# XstractiK_Domination_Player_Connector_V1.net
KiCad netlist of a schematic drawn in EAGLE
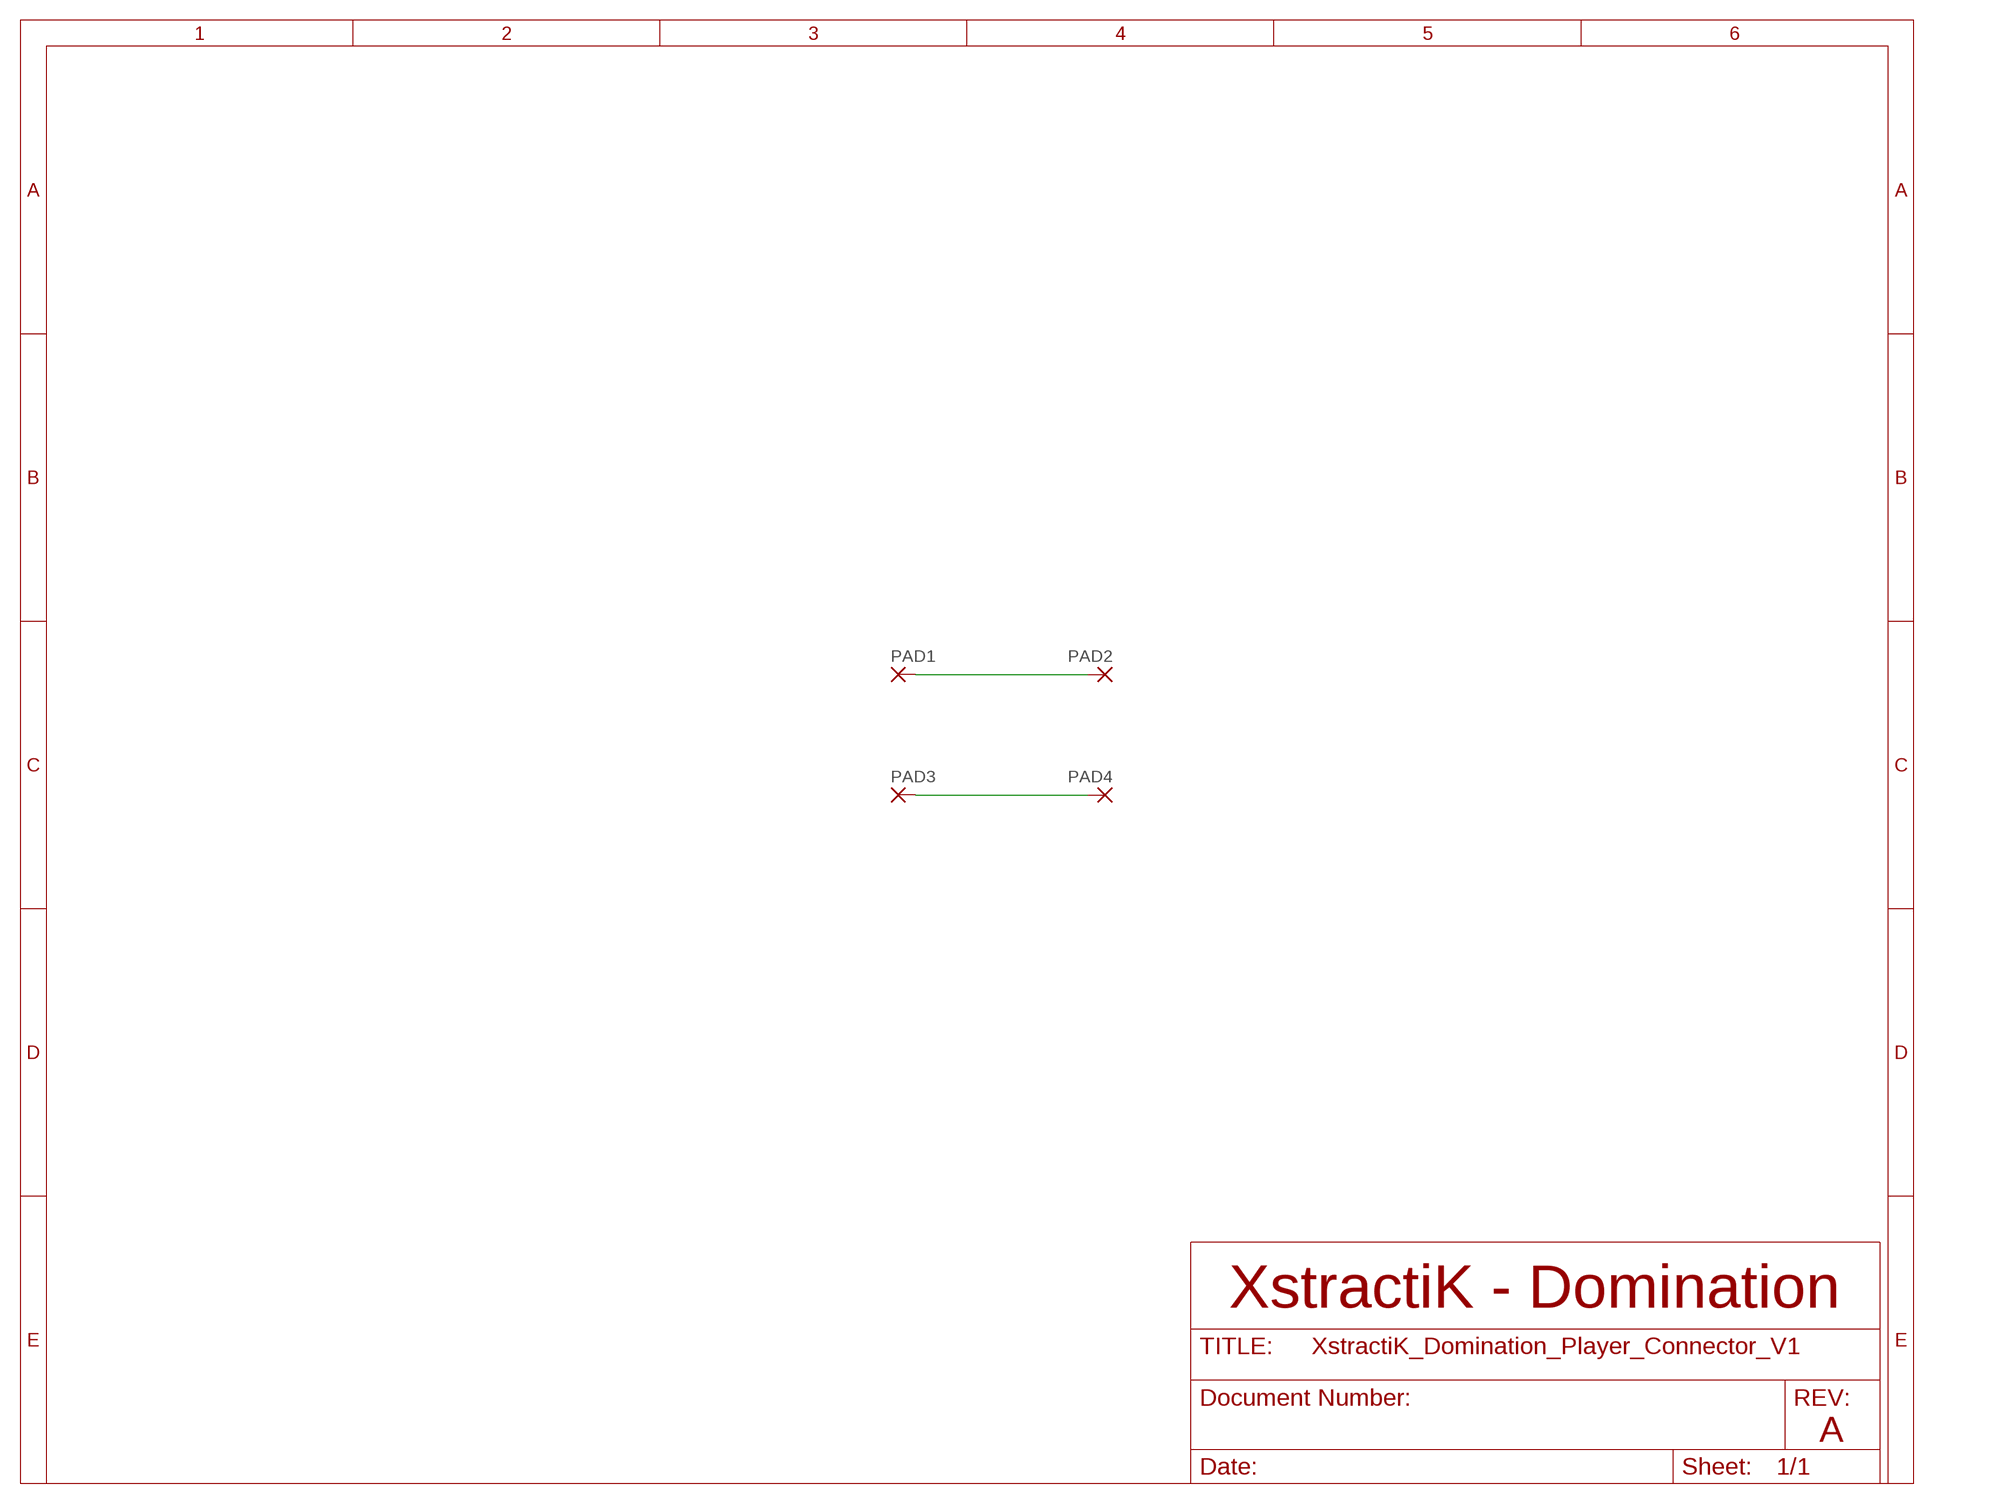
[diagram p0: schematic, sheet 1]

(export (version "E")
  (design (tool "Eeschema 10.0.6"))
  (components
    (comp (ref "PAD1")
      (value "WIREPADSMD1,27-254")
      (footprint "eagle-import:SMD1,27-2,54")
      (libsource (lib "eagle-import") (part "WIREPADSMD1,27-254"))
    )
    (comp (ref "PAD2")
      (value "WIREPADSMD1,27-254")
      (footprint "eagle-import:SMD1,27-2,54")
      (libsource (lib "eagle-import") (part "WIREPADSMD1,27-254"))
    )
    (comp (ref "PAD3")
      (value "WIREPADSMD1,27-254")
      (footprint "eagle-import:SMD1,27-2,54")
      (libsource (lib "eagle-import") (part "WIREPADSMD1,27-254"))
    )
    (comp (ref "PAD4")
      (value "WIREPADSMD1,27-254")
      (footprint "eagle-import:SMD1,27-2,54")
      (libsource (lib "eagle-import") (part "WIREPADSMD1,27-254"))
    )
  )
  (nets
    (net (code "1") (name "Net-(PAD1-P)") (class "Default")
      (node (ref "PAD1") (pin "1") (pinfunction "P_1") (pintype "passive"))
      (node (ref "PAD2") (pin "1") (pinfunction "P_1") (pintype "passive"))
    )
    (net (code "2") (name "Net-(PAD3-P)") (class "Default")
      (node (ref "PAD3") (pin "1") (pinfunction "P_1") (pintype "passive"))
      (node (ref "PAD4") (pin "1") (pinfunction "P_1") (pintype "passive"))
    )
  )
)
